# Exoskeleton_PCB_v1.net
KiCad netlist of a schematic drawn in EAGLE
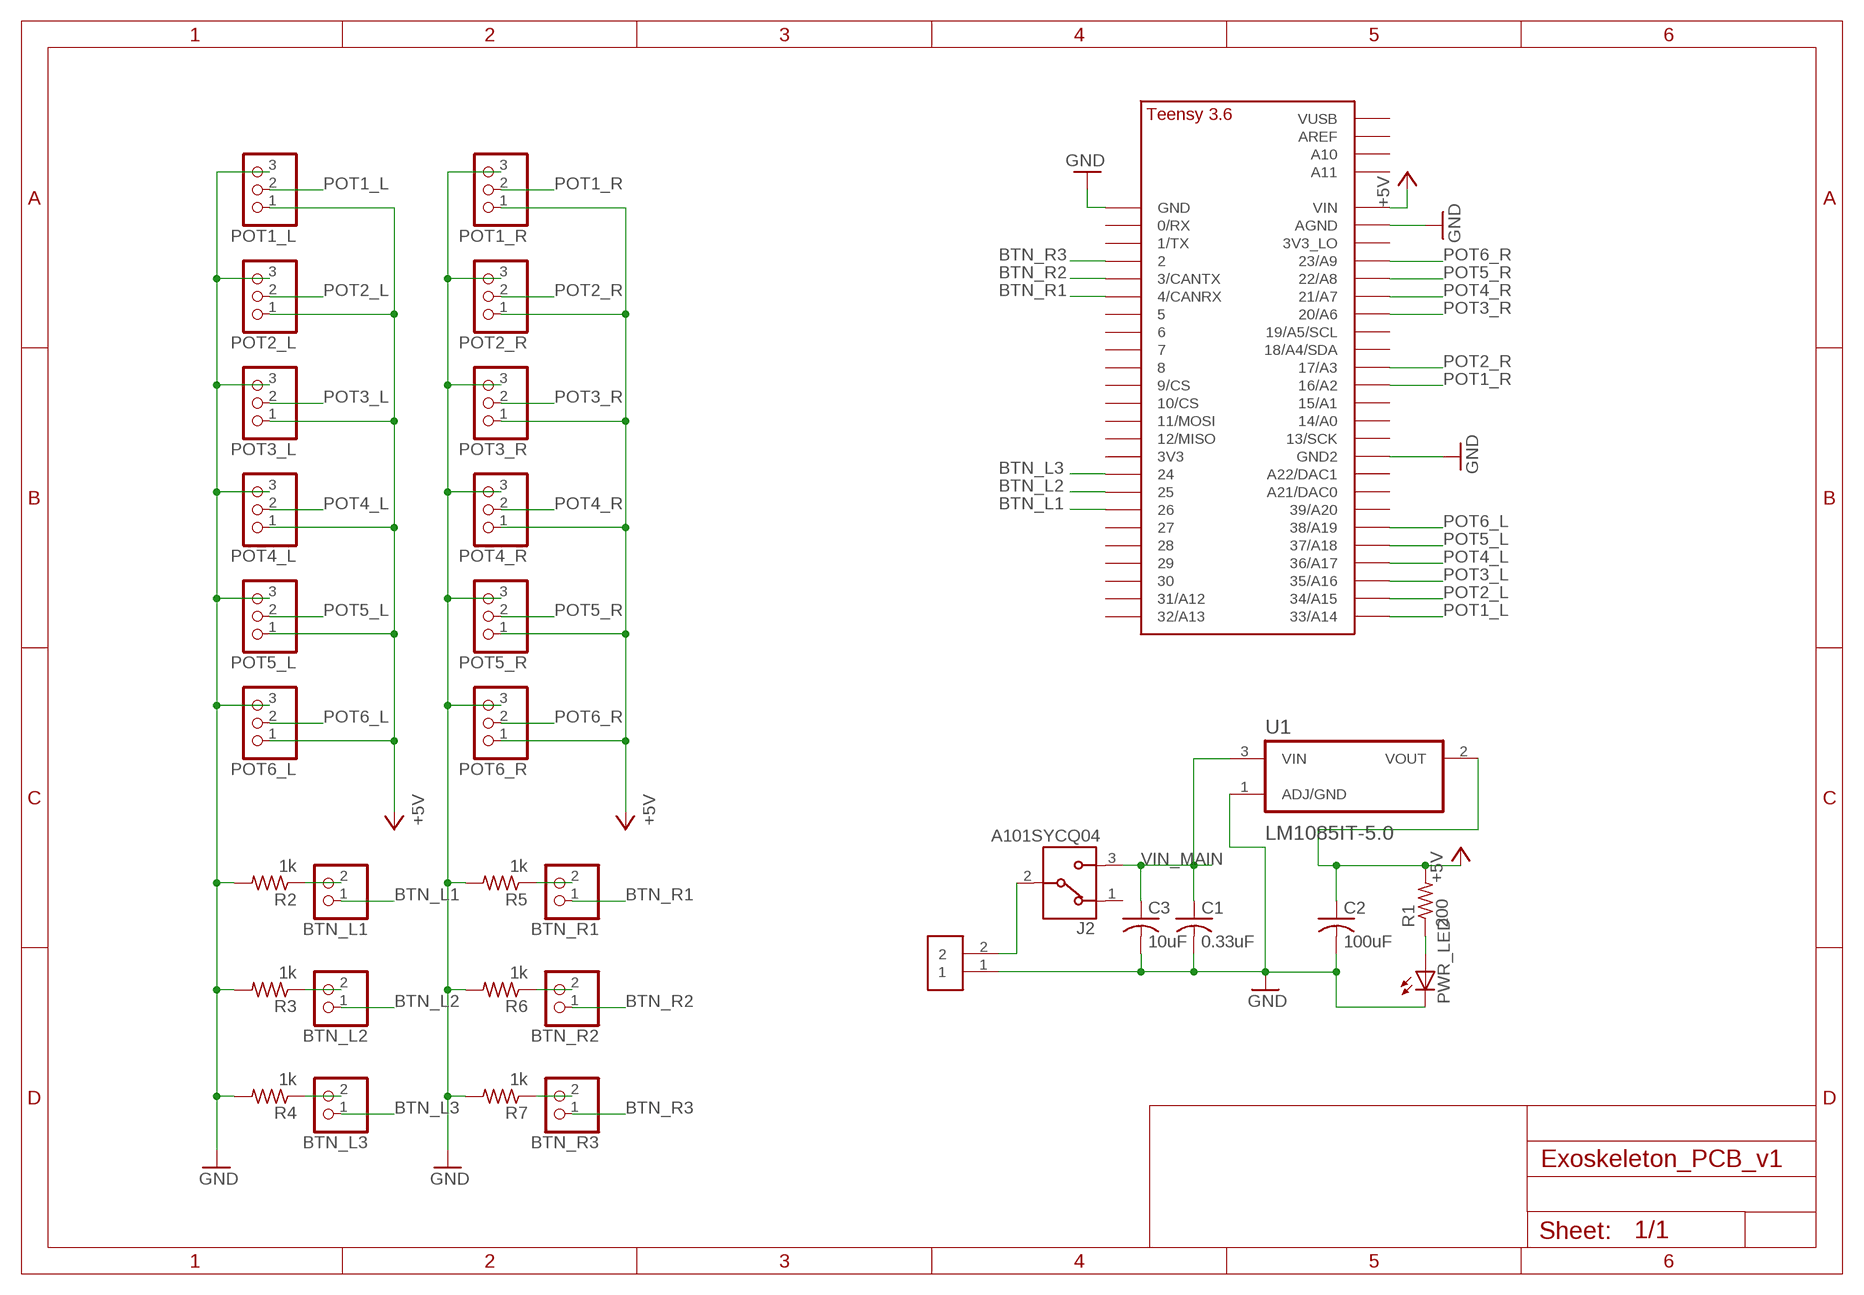
[diagram p0: schematic, sheet 1]

(export (version "E")
  (design (tool "Eeschema 10.0.6"))
  (components
    (comp (ref "BTN_L1")
      (value "PINHD-1X2")
      (footprint "eagle-import:1X02")
      (libsource (lib "eagle-import") (part "PINHD-1X2"))
    )
    (comp (ref "BTN_L2")
      (value "PINHD-1X2")
      (footprint "eagle-import:1X02")
      (libsource (lib "eagle-import") (part "PINHD-1X2"))
    )
    (comp (ref "BTN_L3")
      (value "PINHD-1X2")
      (footprint "eagle-import:1X02")
      (libsource (lib "eagle-import") (part "PINHD-1X2"))
    )
    (comp (ref "BTN_R1")
      (value "PINHD-1X2")
      (footprint "eagle-import:1X02")
      (libsource (lib "eagle-import") (part "PINHD-1X2"))
    )
    (comp (ref "BTN_R2")
      (value "PINHD-1X2")
      (footprint "eagle-import:1X02")
      (libsource (lib "eagle-import") (part "PINHD-1X2"))
    )
    (comp (ref "BTN_R3")
      (value "PINHD-1X2")
      (footprint "eagle-import:1X02")
      (libsource (lib "eagle-import") (part "PINHD-1X2"))
    )
    (comp (ref "C1")
      (value "0.33uF")
      (footprint "eagle-import:C050-030X075")
      (libsource (lib "eagle-import") (part "C-US050-030X075"))
    )
    (comp (ref "C2")
      (value "100uF")
      (footprint "eagle-import:C050-030X075")
      (libsource (lib "eagle-import") (part "C-US050-030X075"))
    )
    (comp (ref "C3")
      (value "10uF")
      (footprint "eagle-import:C050-030X075")
      (libsource (lib "eagle-import") (part "C-US050-030X075"))
    )
    (comp (ref "J1")
      (value "282837-2")
      (footprint "eagle-import:TE_282837-2")
      (fields (field (name "MF") "TE Connectivity"))
      (libsource (lib "eagle-import") (part "282837-2"))
    )
    (comp (ref "J2")
      (value "A101SYCQ04")
      (footprint "eagle-import:TE_A101SYCQ04")
      (fields (field (name "COMMENT") "4-1825136-5") (field (name "MF") "TE Connectivity"))
      (libsource (lib "eagle-import") (part "A101SYCQ04"))
    )
    (comp (ref "POT1_L")
      (value "PINHD-1X3")
      (footprint "eagle-import:1X03")
      (libsource (lib "eagle-import") (part "PINHD-1X3"))
    )
    (comp (ref "POT1_R")
      (value "PINHD-1X3")
      (footprint "eagle-import:1X03")
      (libsource (lib "eagle-import") (part "PINHD-1X3"))
    )
    (comp (ref "POT2_L")
      (value "PINHD-1X3")
      (footprint "eagle-import:1X03")
      (libsource (lib "eagle-import") (part "PINHD-1X3"))
    )
    (comp (ref "POT2_R")
      (value "PINHD-1X3")
      (footprint "eagle-import:1X03")
      (libsource (lib "eagle-import") (part "PINHD-1X3"))
    )
    (comp (ref "POT3_L")
      (value "PINHD-1X3")
      (footprint "eagle-import:1X03")
      (libsource (lib "eagle-import") (part "PINHD-1X3"))
    )
    (comp (ref "POT3_R")
      (value "PINHD-1X3")
      (footprint "eagle-import:1X03")
      (libsource (lib "eagle-import") (part "PINHD-1X3"))
    )
    (comp (ref "POT4_L")
      (value "PINHD-1X3")
      (footprint "eagle-import:1X03")
      (libsource (lib "eagle-import") (part "PINHD-1X3"))
    )
    (comp (ref "POT4_R")
      (value "PINHD-1X3")
      (footprint "eagle-import:1X03")
      (libsource (lib "eagle-import") (part "PINHD-1X3"))
    )
    (comp (ref "POT5_L")
      (value "PINHD-1X3")
      (footprint "eagle-import:1X03")
      (libsource (lib "eagle-import") (part "PINHD-1X3"))
    )
    (comp (ref "POT5_R")
      (value "PINHD-1X3")
      (footprint "eagle-import:1X03")
      (libsource (lib "eagle-import") (part "PINHD-1X3"))
    )
    (comp (ref "POT6_L")
      (value "PINHD-1X3")
      (footprint "eagle-import:1X03")
      (libsource (lib "eagle-import") (part "PINHD-1X3"))
    )
    (comp (ref "POT6_R")
      (value "PINHD-1X3")
      (footprint "eagle-import:1X03")
      (libsource (lib "eagle-import") (part "PINHD-1X3"))
    )
    (comp (ref "PWR_LED")
      (value "LED5MM")
      (footprint "eagle-import:LED5MM")
      (libsource (lib "eagle-import") (part "LED5MM"))
    )
    (comp (ref "R1")
      (value "200")
      (footprint "eagle-import:0207_9")
      (libsource (lib "eagle-import") (part "R-US_0207/9"))
    )
    (comp (ref "R2")
      (value "1k")
      (footprint "eagle-import:0207_9")
      (libsource (lib "eagle-import") (part "R-US_0207/9"))
    )
    (comp (ref "R3")
      (value "1k")
      (footprint "eagle-import:0207_9")
      (libsource (lib "eagle-import") (part "R-US_0207/9"))
    )
    (comp (ref "R4")
      (value "1k")
      (footprint "eagle-import:0207_9")
      (libsource (lib "eagle-import") (part "R-US_0207/9"))
    )
    (comp (ref "R5")
      (value "1k")
      (footprint "eagle-import:0207_9")
      (libsource (lib "eagle-import") (part "R-US_0207/9"))
    )
    (comp (ref "R6")
      (value "1k")
      (footprint "eagle-import:0207_9")
      (libsource (lib "eagle-import") (part "R-US_0207/9"))
    )
    (comp (ref "R7")
      (value "1k")
      (footprint "eagle-import:0207_9")
      (libsource (lib "eagle-import") (part "R-US_0207/9"))
    )
    (comp (ref "U$1")
      (value "TEENSY_3.5/3.6_BASIC")
      (footprint "eagle-import:TEENSY_3.5_3.6_BASIC")
      (libsource (lib "eagle-import") (part "TEENSY_3.5/3.6_BASIC"))
    )
    (comp (ref "U1")
      (value "LM1085IT-5.0")
      (footprint "eagle-import:TO254P1054X470X1955-3")
      (fields (field (name "MF") "Texas Instruments") (field (name "MP") "LM1085IT-5.0/NOPB"))
      (libsource (lib "eagle-import") (part "LM1085IT-5.0"))
    )
  )
  (nets
    (net (code "1") (name "+5V") (class "Default")
      (node (ref "C2") (pin "1") (pinfunction "1_1") (pintype "passive"))
      (node (ref "POT1_L") (pin "1") (pinfunction "1_1") (pintype "passive"))
      (node (ref "POT1_R") (pin "1") (pinfunction "1_1") (pintype "passive"))
      (node (ref "POT2_L") (pin "1") (pinfunction "1_1") (pintype "passive"))
      (node (ref "POT2_R") (pin "1") (pinfunction "1_1") (pintype "passive"))
      (node (ref "POT3_L") (pin "1") (pinfunction "1_1") (pintype "passive"))
      (node (ref "POT3_R") (pin "1") (pinfunction "1_1") (pintype "passive"))
      (node (ref "POT4_L") (pin "1") (pinfunction "1_1") (pintype "passive"))
      (node (ref "POT4_R") (pin "1") (pinfunction "1_1") (pintype "passive"))
      (node (ref "POT5_L") (pin "1") (pinfunction "1_1") (pintype "passive"))
      (node (ref "POT5_R") (pin "1") (pinfunction "1_1") (pintype "passive"))
      (node (ref "POT6_L") (pin "1") (pinfunction "1_1") (pintype "passive"))
      (node (ref "POT6_R") (pin "1") (pinfunction "1_1") (pintype "passive"))
      (node (ref "R1") (pin "2") (pinfunction "2_2") (pintype "passive"))
      (node (ref "U$1") (pin "VIN") (pinfunction "VIN_VIN") (pintype "bidirectional"))
      (node (ref "U1") (pin "2") (pinfunction "VOUT_2") (pintype "output"))
    )
    (net (code "2") (name "/BTN_L1") (class "Default")
      (node (ref "BTN_L1") (pin "1") (pinfunction "1_1") (pintype "passive"))
      (node (ref "U$1") (pin "26") (pinfunction "26_26") (pintype "bidirectional"))
    )
    (net (code "3") (name "/BTN_L2") (class "Default")
      (node (ref "BTN_L2") (pin "1") (pinfunction "1_1") (pintype "passive"))
      (node (ref "U$1") (pin "25") (pinfunction "25_25") (pintype "bidirectional"))
    )
    (net (code "4") (name "/BTN_L3") (class "Default")
      (node (ref "BTN_L3") (pin "1") (pinfunction "1_1") (pintype "passive"))
      (node (ref "U$1") (pin "24") (pinfunction "24_24") (pintype "bidirectional"))
    )
    (net (code "5") (name "/BTN_R1") (class "Default")
      (node (ref "BTN_R1") (pin "1") (pinfunction "1_1") (pintype "passive"))
      (node (ref "U$1") (pin "4/CANRX") (pinfunction "4/CANRX_4/CANRX") (pintype "bidirectional"))
    )
    (net (code "6") (name "/BTN_R2") (class "Default")
      (node (ref "BTN_R2") (pin "1") (pinfunction "1_1") (pintype "passive"))
      (node (ref "U$1") (pin "3/CANTX") (pinfunction "3/CANTX_3/CANTX") (pintype "bidirectional"))
    )
    (net (code "7") (name "/BTN_R3") (class "Default")
      (node (ref "BTN_R3") (pin "1") (pinfunction "1_1") (pintype "passive"))
      (node (ref "U$1") (pin "2") (pinfunction "2_2") (pintype "bidirectional"))
    )
    (net (code "8") (name "/POT1_L") (class "Default")
      (node (ref "POT1_L") (pin "2") (pinfunction "2_2") (pintype "passive"))
      (node (ref "U$1") (pin "33/A14") (pinfunction "33/A14_33/A14") (pintype "bidirectional"))
    )
    (net (code "9") (name "/POT1_R") (class "Default")
      (node (ref "POT1_R") (pin "2") (pinfunction "2_2") (pintype "passive"))
      (node (ref "U$1") (pin "16/A2") (pinfunction "16/A2_16/A2") (pintype "bidirectional"))
    )
    (net (code "10") (name "/POT2_L") (class "Default")
      (node (ref "POT2_L") (pin "2") (pinfunction "2_2") (pintype "passive"))
      (node (ref "U$1") (pin "34/A15") (pinfunction "34/A15_34/A15") (pintype "bidirectional"))
    )
    (net (code "11") (name "/POT2_R") (class "Default")
      (node (ref "POT2_R") (pin "2") (pinfunction "2_2") (pintype "passive"))
      (node (ref "U$1") (pin "17/A3") (pinfunction "17/A3_17/A3") (pintype "bidirectional"))
    )
    (net (code "12") (name "/POT3_L") (class "Default")
      (node (ref "POT3_L") (pin "2") (pinfunction "2_2") (pintype "passive"))
      (node (ref "U$1") (pin "35/A16") (pinfunction "35/A16_35/A16") (pintype "bidirectional"))
    )
    (net (code "13") (name "/POT3_R") (class "Default")
      (node (ref "POT3_R") (pin "2") (pinfunction "2_2") (pintype "passive"))
      (node (ref "U$1") (pin "20/A6") (pinfunction "20/A6_20/A6") (pintype "bidirectional"))
    )
    (net (code "14") (name "/POT4_L") (class "Default")
      (node (ref "POT4_L") (pin "2") (pinfunction "2_2") (pintype "passive"))
      (node (ref "U$1") (pin "36/A17") (pinfunction "36/A17_36/A17") (pintype "bidirectional"))
    )
    (net (code "15") (name "/POT4_R") (class "Default")
      (node (ref "POT4_R") (pin "2") (pinfunction "2_2") (pintype "passive"))
      (node (ref "U$1") (pin "21/A7") (pinfunction "21/A7_21/A7") (pintype "bidirectional"))
    )
    (net (code "16") (name "/POT5_L") (class "Default")
      (node (ref "POT5_L") (pin "2") (pinfunction "2_2") (pintype "passive"))
      (node (ref "U$1") (pin "37/A18") (pinfunction "37/A18_37/A18") (pintype "bidirectional"))
    )
    (net (code "17") (name "/POT5_R") (class "Default")
      (node (ref "POT5_R") (pin "2") (pinfunction "2_2") (pintype "passive"))
      (node (ref "U$1") (pin "22/A8") (pinfunction "22/A8_22/A8") (pintype "bidirectional"))
    )
    (net (code "18") (name "/POT6_L") (class "Default")
      (node (ref "POT6_L") (pin "2") (pinfunction "2_2") (pintype "passive"))
      (node (ref "U$1") (pin "38/A19") (pinfunction "38/A19_38/A19") (pintype "bidirectional"))
    )
    (net (code "19") (name "/POT6_R") (class "Default")
      (node (ref "POT6_R") (pin "2") (pinfunction "2_2") (pintype "passive"))
      (node (ref "U$1") (pin "23/A9") (pinfunction "23/A9_23/A9") (pintype "bidirectional"))
    )
    (net (code "20") (name "/VIN_MAIN") (class "Default")
      (node (ref "C1") (pin "1") (pinfunction "1_1") (pintype "passive"))
      (node (ref "C3") (pin "1") (pinfunction "1_1") (pintype "passive"))
      (node (ref "J2") (pin "3") (pinfunction "3_3") (pintype "passive"))
      (node (ref "U1") (pin "3") (pinfunction "VIN_3") (pintype "input"))
    )
    (net (code "21") (name "GND") (class "Default")
      (node (ref "C1") (pin "2") (pinfunction "2_2") (pintype "passive"))
      (node (ref "C2") (pin "2") (pinfunction "2_2") (pintype "passive"))
      (node (ref "C3") (pin "2") (pinfunction "2_2") (pintype "passive"))
      (node (ref "J1") (pin "1") (pinfunction "1_1") (pintype "passive"))
      (node (ref "POT1_L") (pin "3") (pinfunction "3_3") (pintype "passive"))
      (node (ref "POT1_R") (pin "3") (pinfunction "3_3") (pintype "passive"))
      (node (ref "POT2_L") (pin "3") (pinfunction "3_3") (pintype "passive"))
      (node (ref "POT2_R") (pin "3") (pinfunction "3_3") (pintype "passive"))
      (node (ref "POT3_L") (pin "3") (pinfunction "3_3") (pintype "passive"))
      (node (ref "POT3_R") (pin "3") (pinfunction "3_3") (pintype "passive"))
      (node (ref "POT4_L") (pin "3") (pinfunction "3_3") (pintype "passive"))
      (node (ref "POT4_R") (pin "3") (pinfunction "3_3") (pintype "passive"))
      (node (ref "POT5_L") (pin "3") (pinfunction "3_3") (pintype "passive"))
      (node (ref "POT5_R") (pin "3") (pinfunction "3_3") (pintype "passive"))
      (node (ref "POT6_L") (pin "3") (pinfunction "3_3") (pintype "passive"))
      (node (ref "POT6_R") (pin "3") (pinfunction "3_3") (pintype "passive"))
      (node (ref "PWR_LED") (pin "K") (pinfunction "C_K") (pintype "passive"))
      (node (ref "R2") (pin "2") (pinfunction "2_2") (pintype "passive"))
      (node (ref "R3") (pin "2") (pinfunction "2_2") (pintype "passive"))
      (node (ref "R4") (pin "2") (pinfunction "2_2") (pintype "passive"))
      (node (ref "R5") (pin "2") (pinfunction "2_2") (pintype "passive"))
      (node (ref "R6") (pin "2") (pinfunction "2_2") (pintype "passive"))
      (node (ref "R7") (pin "2") (pinfunction "2_2") (pintype "passive"))
      (node (ref "U$1") (pin "AGND") (pinfunction "AGND_AGND") (pintype "bidirectional"))
      (node (ref "U$1") (pin "GND") (pinfunction "GND_GND") (pintype "bidirectional"))
      (node (ref "U$1") (pin "GND2") (pinfunction "GND2_GND2") (pintype "bidirectional"))
      (node (ref "U1") (pin "1") (pinfunction "ADJ/GND_1") (pintype "bidirectional"))
    )
    (net (code "22") (name "Net-(BTN_L1-Pad2)") (class "Default")
      (node (ref "BTN_L1") (pin "2") (pinfunction "2_2") (pintype "passive"))
      (node (ref "R2") (pin "1") (pinfunction "1_1") (pintype "passive"))
    )
    (net (code "23") (name "Net-(BTN_L2-Pad2)") (class "Default")
      (node (ref "BTN_L2") (pin "2") (pinfunction "2_2") (pintype "passive"))
      (node (ref "R3") (pin "1") (pinfunction "1_1") (pintype "passive"))
    )
    (net (code "24") (name "Net-(BTN_L3-Pad2)") (class "Default")
      (node (ref "BTN_L3") (pin "2") (pinfunction "2_2") (pintype "passive"))
      (node (ref "R4") (pin "1") (pinfunction "1_1") (pintype "passive"))
    )
    (net (code "25") (name "Net-(BTN_R1-Pad2)") (class "Default")
      (node (ref "BTN_R1") (pin "2") (pinfunction "2_2") (pintype "passive"))
      (node (ref "R5") (pin "1") (pinfunction "1_1") (pintype "passive"))
    )
    (net (code "26") (name "Net-(BTN_R2-Pad2)") (class "Default")
      (node (ref "BTN_R2") (pin "2") (pinfunction "2_2") (pintype "passive"))
      (node (ref "R6") (pin "1") (pinfunction "1_1") (pintype "passive"))
    )
    (net (code "27") (name "Net-(BTN_R3-Pad2)") (class "Default")
      (node (ref "BTN_R3") (pin "2") (pinfunction "2_2") (pintype "passive"))
      (node (ref "R7") (pin "1") (pinfunction "1_1") (pintype "passive"))
    )
    (net (code "28") (name "Net-(J1-Pad2)") (class "Default")
      (node (ref "J1") (pin "2") (pinfunction "2_2") (pintype "passive"))
      (node (ref "J2") (pin "2") (pinfunction "2_2") (pintype "passive"))
    )
    (net (code "29") (name "Net-(PWR_LED-PadA)") (class "Default")
      (node (ref "PWR_LED") (pin "A") (pinfunction "A_A") (pintype "passive"))
      (node (ref "R1") (pin "1") (pinfunction "1_1") (pintype "passive"))
    )
    (net (code "30") (name "unconnected-(J2-Pad1)") (class "Default")
      (node (ref "J2") (pin "1") (pinfunction "1_1") (pintype "passive"))
    )
    (net (code "31") (name "unconnected-(U$1-A21{slash}DAC0-Pad21{slash}DAC0)") (class "Default")
      (node (ref "U$1") (pin "21/DAC0") (pinfunction "A21/DAC0_21/DAC0") (pintype "bidirectional"))
    )
    (net (code "32") (name "unconnected-(U$1-Pad0{slash}RX)") (class "Default")
      (node (ref "U$1") (pin "0/RX") (pinfunction "0/RX_0/RX") (pintype "bidirectional"))
    )
    (net (code "33") (name "unconnected-(U$1-Pad1{slash}TX)") (class "Default")
      (node (ref "U$1") (pin "1/TX") (pinfunction "1/TX_1/TX") (pintype "bidirectional"))
    )
    (net (code "34") (name "unconnected-(U$1-Pad3V3)") (class "Default")
      (node (ref "U$1") (pin "3V3") (pinfunction "3V3_3V3") (pintype "bidirectional"))
    )
    (net (code "35") (name "unconnected-(U$1-Pad3V3_LO)") (class "Default")
      (node (ref "U$1") (pin "3V3_LO") (pinfunction "3V3_LO_3V3_LO") (pintype "bidirectional"))
    )
    (net (code "36") (name "unconnected-(U$1-Pad5)") (class "Default")
      (node (ref "U$1") (pin "5") (pinfunction "5_5") (pintype "bidirectional"))
    )
    (net (code "37") (name "unconnected-(U$1-Pad6)") (class "Default")
      (node (ref "U$1") (pin "6") (pinfunction "6_6") (pintype "bidirectional"))
    )
    (net (code "38") (name "unconnected-(U$1-Pad7)") (class "Default")
      (node (ref "U$1") (pin "7") (pinfunction "7_7") (pintype "bidirectional"))
    )
    (net (code "39") (name "unconnected-(U$1-Pad8)") (class "Default")
      (node (ref "U$1") (pin "8") (pinfunction "8_8") (pintype "bidirectional"))
    )
    (net (code "40") (name "unconnected-(U$1-Pad9{slash}CS)") (class "Default")
      (node (ref "U$1") (pin "9/CS") (pinfunction "9/CS_9/CS") (pintype "bidirectional"))
    )
    (net (code "41") (name "unconnected-(U$1-Pad10{slash}CS)") (class "Default")
      (node (ref "U$1") (pin "10/CS") (pinfunction "10/CS_10/CS") (pintype "bidirectional"))
    )
    (net (code "42") (name "unconnected-(U$1-Pad11{slash}MOSI)") (class "Default")
      (node (ref "U$1") (pin "11/MOSI") (pinfunction "11/MOSI_11/MOSI") (pintype "bidirectional"))
    )
    (net (code "43") (name "unconnected-(U$1-Pad12{slash}MISO)") (class "Default")
      (node (ref "U$1") (pin "12/MISO") (pinfunction "12/MISO_12/MISO") (pintype "bidirectional"))
    )
    (net (code "44") (name "unconnected-(U$1-Pad13{slash}SCK)") (class "Default")
      (node (ref "U$1") (pin "13/SCK") (pinfunction "13/SCK_13/SCK") (pintype "bidirectional"))
    )
    (net (code "45") (name "unconnected-(U$1-Pad14{slash}A0)") (class "Default")
      (node (ref "U$1") (pin "14/A0") (pinfunction "14/A0_14/A0") (pintype "bidirectional"))
    )
    (net (code "46") (name "unconnected-(U$1-Pad15{slash}A1)") (class "Default")
      (node (ref "U$1") (pin "15/A1") (pinfunction "15/A1_15/A1") (pintype "bidirectional"))
    )
    (net (code "47") (name "unconnected-(U$1-Pad18{slash}A4{slash}SDA)") (class "Default")
      (node (ref "U$1") (pin "18/A4/SDA") (pinfunction "18/A4/SDA_18/A4/SDA") (pintype "bidirectional"))
    )
    (net (code "48") (name "unconnected-(U$1-Pad19{slash}A5{slash}SCL)") (class "Default")
      (node (ref "U$1") (pin "19/A5/SCL") (pinfunction "19/A5/SCL_19/A5/SCL") (pintype "bidirectional"))
    )
    (net (code "49") (name "unconnected-(U$1-Pad27)") (class "Default")
      (node (ref "U$1") (pin "27") (pinfunction "27_27") (pintype "bidirectional"))
    )
    (net (code "50") (name "unconnected-(U$1-Pad28)") (class "Default")
      (node (ref "U$1") (pin "28") (pinfunction "28_28") (pintype "bidirectional"))
    )
    (net (code "51") (name "unconnected-(U$1-Pad29)") (class "Default")
      (node (ref "U$1") (pin "29") (pinfunction "29_29") (pintype "bidirectional"))
    )
    (net (code "52") (name "unconnected-(U$1-Pad30)") (class "Default")
      (node (ref "U$1") (pin "30") (pinfunction "30_30") (pintype "bidirectional"))
    )
    (net (code "53") (name "unconnected-(U$1-Pad31{slash}A12)") (class "Default")
      (node (ref "U$1") (pin "31/A12") (pinfunction "31/A12_31/A12") (pintype "bidirectional"))
    )
    (net (code "54") (name "unconnected-(U$1-Pad32{slash}A13)") (class "Default")
      (node (ref "U$1") (pin "32/A13") (pinfunction "32/A13_32/A13") (pintype "bidirectional"))
    )
    (net (code "55") (name "unconnected-(U$1-Pad39{slash}A20)") (class "Default")
      (node (ref "U$1") (pin "39/A20") (pinfunction "39/A20_39/A20") (pintype "bidirectional"))
    )
    (net (code "56") (name "unconnected-(U$1-PadA10)") (class "Default")
      (node (ref "U$1") (pin "A10") (pinfunction "A10_A10") (pintype "bidirectional"))
    )
    (net (code "57") (name "unconnected-(U$1-PadA11)") (class "Default")
      (node (ref "U$1") (pin "A11") (pinfunction "A11_A11") (pintype "bidirectional"))
    )
    (net (code "58") (name "unconnected-(U$1-PadA22{slash}DAC1)") (class "Default")
      (node (ref "U$1") (pin "A22/DAC1") (pinfunction "A22/DAC1_A22/DAC1") (pintype "bidirectional"))
    )
    (net (code "59") (name "unconnected-(U$1-PadAREF)") (class "Default")
      (node (ref "U$1") (pin "AREF") (pinfunction "AREF_AREF") (pintype "bidirectional"))
    )
    (net (code "60") (name "unconnected-(U$1-PadVUSB)") (class "Default")
      (node (ref "U$1") (pin "VUSB") (pinfunction "VUSB_VUSB") (pintype "bidirectional"))
    )
  )
)
